# MV500-BASIC-TOP.net
KiCad netlist of a schematic drawn in EAGLE
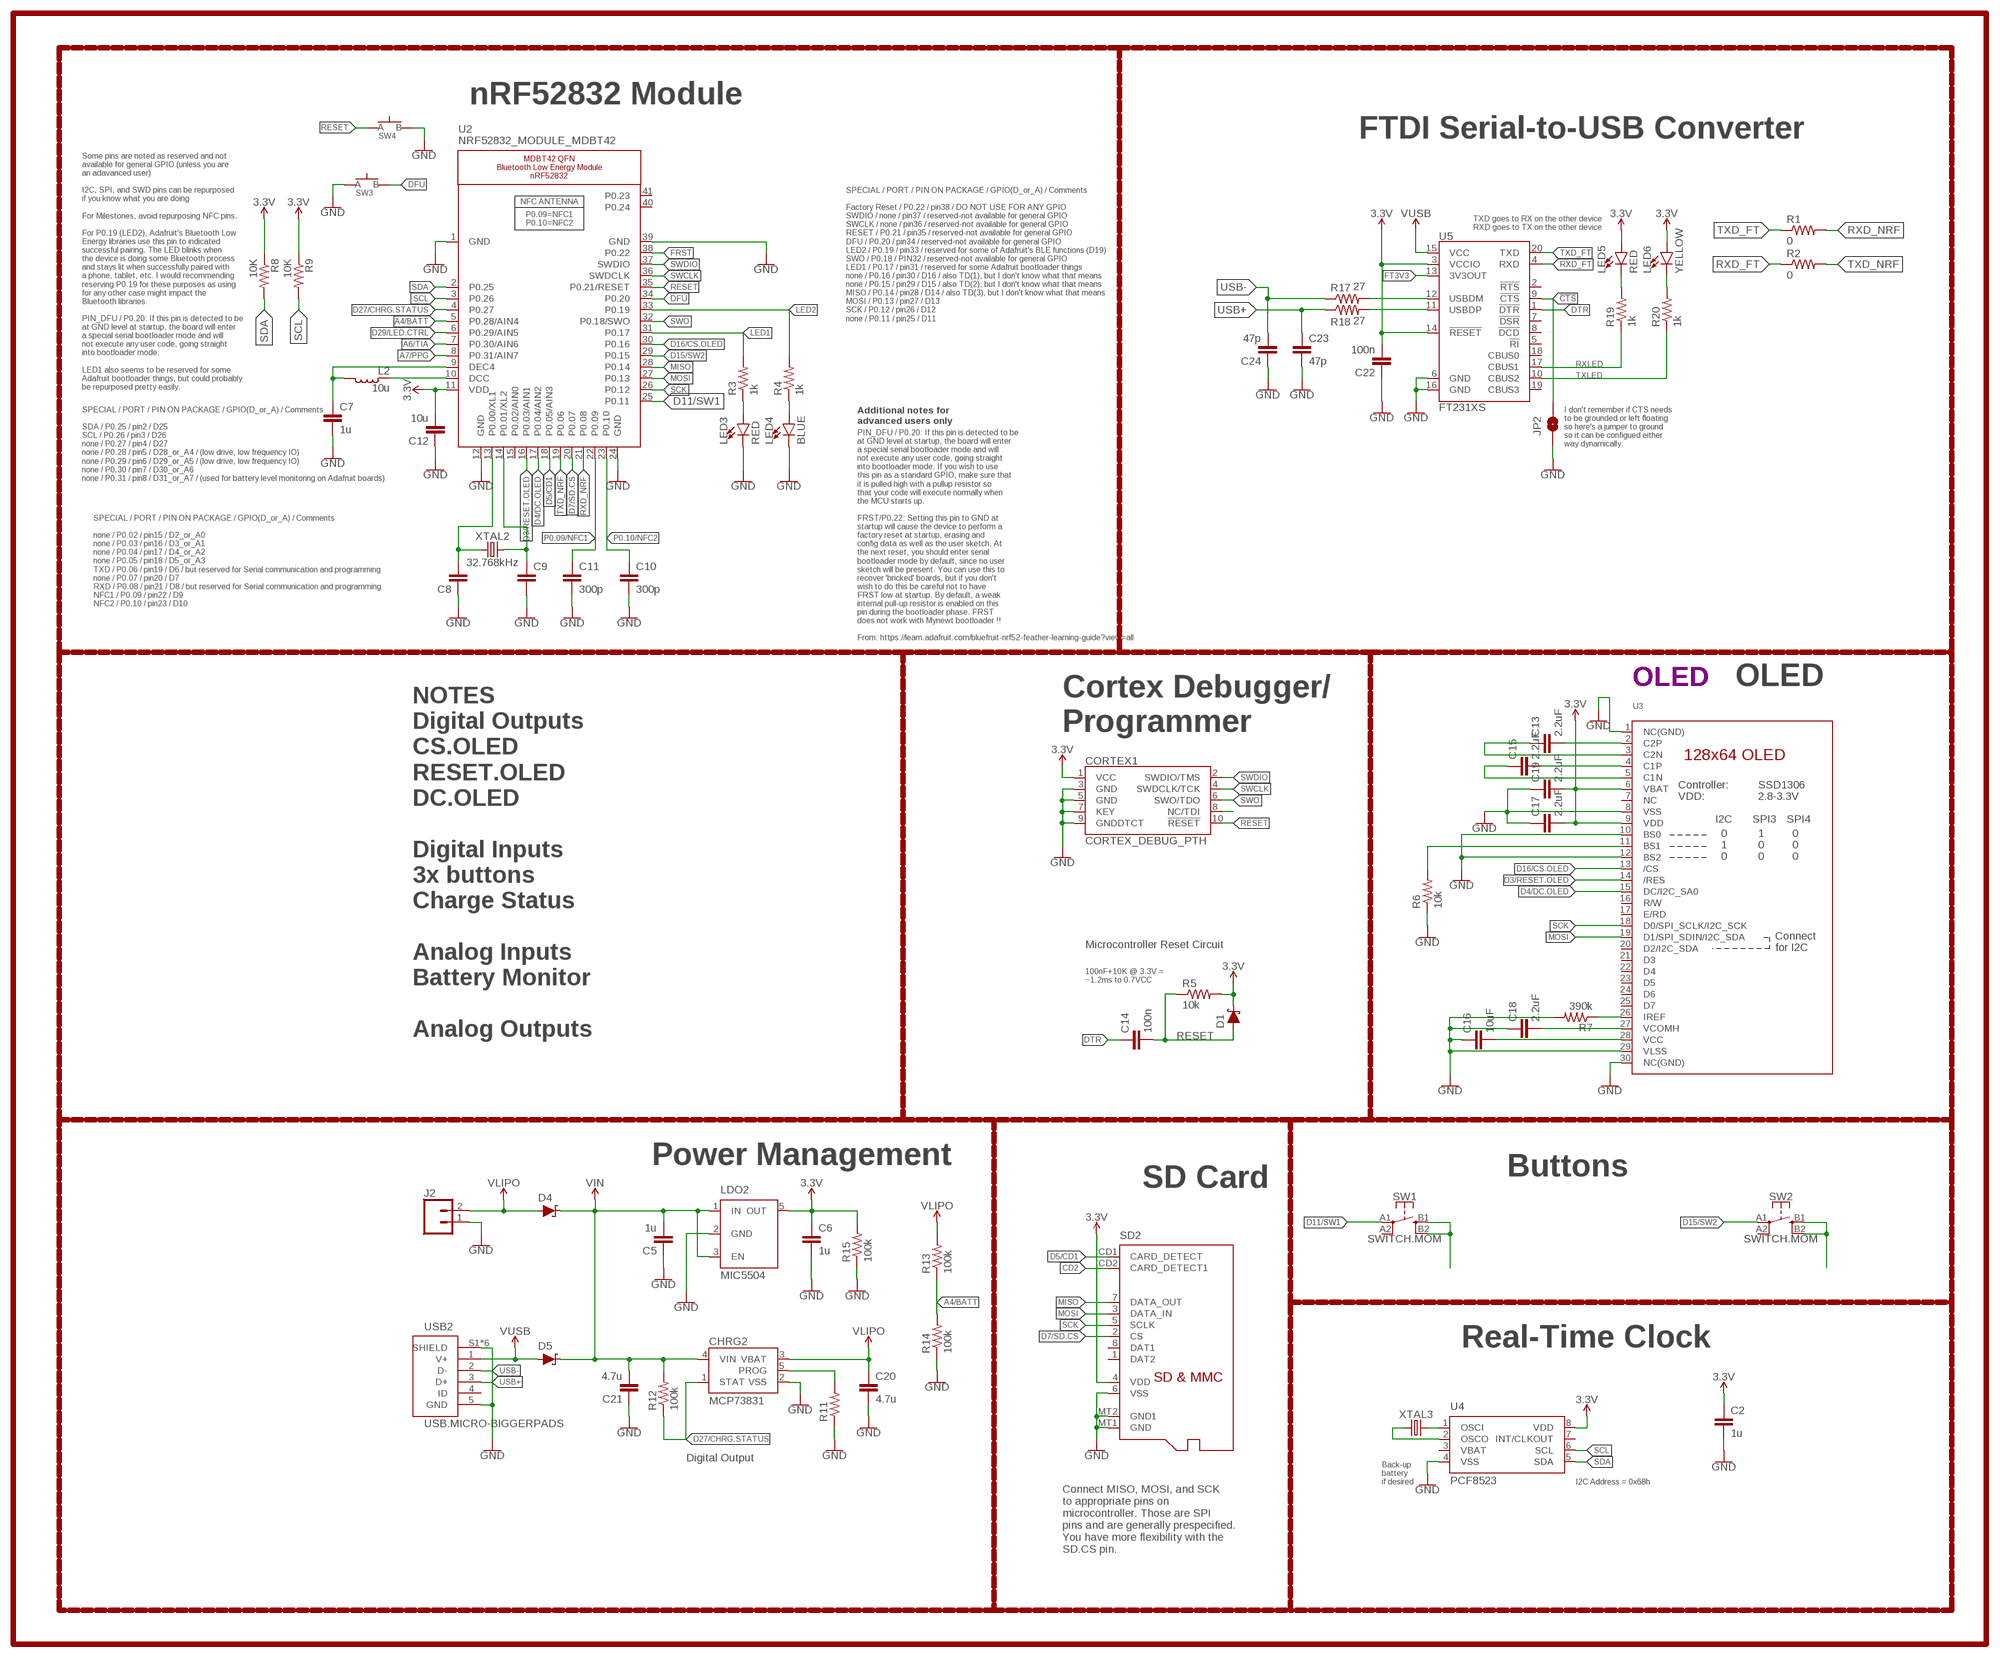
[diagram p0: schematic, sheet 1]

(export (version "E")
  (design (tool "Eeschema 10.0.6"))
  (components
    (comp (ref "C2")
      (value "1u")
      (footprint "eagle-import:C0603")
      (libsource (lib "eagle-import") (part "CAPACITOR0603"))
    )
    (comp (ref "C5")
      (value "1u")
      (footprint "eagle-import:C0603")
      (libsource (lib "eagle-import") (part "CAPACITOR0603"))
    )
    (comp (ref "C6")
      (value "1u")
      (footprint "eagle-import:C0603")
      (libsource (lib "eagle-import") (part "CAPACITOR0603"))
    )
    (comp (ref "C7")
      (value "1u")
      (footprint "eagle-import:C0603")
      (libsource (lib "eagle-import") (part "CAPACITOR0603"))
    )
    (comp (ref "C8")
      (value "CAPACITOR0603")
      (footprint "eagle-import:C0603")
      (libsource (lib "eagle-import") (part "CAPACITOR0603"))
    )
    (comp (ref "C9")
      (value "CAPACITOR0603")
      (footprint "eagle-import:C0603")
      (libsource (lib "eagle-import") (part "CAPACITOR0603"))
    )
    (comp (ref "C10")
      (value "300p")
      (footprint "eagle-import:C0603")
      (libsource (lib "eagle-import") (part "CAPACITOR0603"))
    )
    (comp (ref "C11")
      (value "300p")
      (footprint "eagle-import:C0603")
      (libsource (lib "eagle-import") (part "CAPACITOR0603"))
    )
    (comp (ref "C12")
      (value "10u")
      (footprint "eagle-import:C0805")
      (libsource (lib "eagle-import") (part "CAPACITOR0805"))
    )
    (comp (ref "C13")
      (value "2.2uF")
      (footprint "eagle-import:C0402")
      (libsource (lib "eagle-import") (part "CAPACITOR0402"))
    )
    (comp (ref "C14")
      (value "100n")
      (footprint "eagle-import:C0603")
      (libsource (lib "eagle-import") (part "CAPACITOR0603"))
    )
    (comp (ref "C15")
      (value "2.2uF")
      (footprint "eagle-import:C0402")
      (libsource (lib "eagle-import") (part "CAPACITOR0402"))
    )
    (comp (ref "C16")
      (value "10uF")
      (footprint "eagle-import:C0603")
      (libsource (lib "eagle-import") (part "CAPACITOR0603"))
    )
    (comp (ref "C17")
      (value "2.2uF")
      (footprint "eagle-import:C0402")
      (libsource (lib "eagle-import") (part "CAPACITOR0402"))
    )
    (comp (ref "C18")
      (value "2.2uF")
      (footprint "eagle-import:C0402")
      (libsource (lib "eagle-import") (part "CAPACITOR0402"))
    )
    (comp (ref "C19")
      (value "2.2uF")
      (footprint "eagle-import:C0402")
      (libsource (lib "eagle-import") (part "CAPACITOR0402"))
    )
    (comp (ref "C20")
      (value "4.7u")
      (footprint "eagle-import:C0603")
      (libsource (lib "eagle-import") (part "CAPACITOR0603"))
    )
    (comp (ref "C21")
      (value "4.7u")
      (footprint "eagle-import:C0603")
      (libsource (lib "eagle-import") (part "CAPACITOR0603"))
    )
    (comp (ref "C22")
      (value "100n")
      (footprint "eagle-import:C0603")
      (libsource (lib "eagle-import") (part "CAPACITOR0603"))
    )
    (comp (ref "C23")
      (value "47p")
      (footprint "eagle-import:C0603")
      (libsource (lib "eagle-import") (part "CAPACITOR0603"))
    )
    (comp (ref "C24")
      (value "47p")
      (footprint "eagle-import:C0603")
      (libsource (lib "eagle-import") (part "CAPACITOR0603"))
    )
    (comp (ref "CHRG2")
      (value "MCP73831")
      (footprint "eagle-import:SOT23-5")
      (libsource (lib "eagle-import") (part "MCP73831"))
    )
    (comp (ref "CORTEX1")
      (value "CORTEX_DEBUG_PTH")
      (footprint "eagle-import:2X5-PTH-1.27MM")
      (libsource (lib "eagle-import") (part "CORTEX_DEBUG_PTH"))
    )
    (comp (ref "D1")
      (value "SCHOTTKY-USC")
      (footprint "eagle-import:USC")
      (libsource (lib "eagle-import") (part "SCHOTTKY-USC"))
    )
    (comp (ref "D4")
      (value "SCHOTTKY-USC")
      (footprint "eagle-import:USC")
      (libsource (lib "eagle-import") (part "SCHOTTKY-USC"))
    )
    (comp (ref "D5")
      (value "SCHOTTKY-USC")
      (footprint "eagle-import:USC")
      (libsource (lib "eagle-import") (part "SCHOTTKY-USC"))
    )
    (comp (ref "J2")
      (value "CONN_02")
      (footprint "eagle-import:1X02")
      (libsource (lib "eagle-import") (part "CONN_02"))
    )
    (comp (ref "JP2")
      (value "JUMPER-SMT_2_NO_SILK")
      (footprint "eagle-import:SMT-JUMPER_2_NO_SILK")
      (libsource (lib "eagle-import") (part "JUMPER-SMT_2_NO_SILK"))
    )
    (comp (ref "L2")
      (value "10u")
      (footprint "eagle-import:L0603")
      (libsource (lib "eagle-import") (part "INDUCTOR0603"))
    )
    (comp (ref "LDO2")
      (value "MIC5504")
      (footprint "eagle-import:SOT23-5")
      (libsource (lib "eagle-import") (part "MIC5504"))
    )
    (comp (ref "LED3")
      (value "RED")
      (footprint "eagle-import:LED-0603")
      (libsource (lib "eagle-import") (part "LED0603"))
    )
    (comp (ref "LED4")
      (value "BLUE")
      (footprint "eagle-import:LED-0603")
      (libsource (lib "eagle-import") (part "LED0603"))
    )
    (comp (ref "LED5")
      (value "RED")
      (footprint "eagle-import:LED-0603")
      (libsource (lib "eagle-import") (part "LED0603"))
    )
    (comp (ref "LED6")
      (value "YELLOW")
      (footprint "eagle-import:LED-0603")
      (libsource (lib "eagle-import") (part "LED0603"))
    )
    (comp (ref "R1")
      (value "0")
      (footprint "eagle-import:R0603")
      (libsource (lib "eagle-import") (part "RESISTOR0603"))
    )
    (comp (ref "R2")
      (value "0")
      (footprint "eagle-import:R0603")
      (libsource (lib "eagle-import") (part "RESISTOR0603"))
    )
    (comp (ref "R3")
      (value "1k")
      (footprint "eagle-import:R0603")
      (libsource (lib "eagle-import") (part "RESISTOR0603"))
    )
    (comp (ref "R4")
      (value "1k")
      (footprint "eagle-import:R0603")
      (libsource (lib "eagle-import") (part "RESISTOR0603"))
    )
    (comp (ref "R5")
      (value "10k")
      (footprint "eagle-import:R0603")
      (libsource (lib "eagle-import") (part "RESISTOR0603"))
    )
    (comp (ref "R6")
      (value "10k")
      (footprint "eagle-import:R0603")
      (libsource (lib "eagle-import") (part "RESISTOR0603"))
    )
    (comp (ref "R7")
      (value "390k")
      (footprint "eagle-import:R0603")
      (libsource (lib "eagle-import") (part "RESISTOR0603"))
    )
    (comp (ref "R8")
      (value "10K")
      (footprint "eagle-import:R0603")
      (libsource (lib "eagle-import") (part "RESISTOR0603"))
    )
    (comp (ref "R9")
      (value "10K")
      (footprint "eagle-import:R0603")
      (libsource (lib "eagle-import") (part "RESISTOR0603"))
    )
    (comp (ref "R11")
      (value "RESISTOR0603")
      (footprint "eagle-import:R0603")
      (libsource (lib "eagle-import") (part "RESISTOR0603"))
    )
    (comp (ref "R12")
      (value "100k")
      (footprint "eagle-import:R0603")
      (libsource (lib "eagle-import") (part "RESISTOR0603"))
    )
    (comp (ref "R13")
      (value "100k")
      (footprint "eagle-import:R0603")
      (libsource (lib "eagle-import") (part "RESISTOR0603"))
    )
    (comp (ref "R14")
      (value "100k")
      (footprint "eagle-import:R0603")
      (libsource (lib "eagle-import") (part "RESISTOR0603"))
    )
    (comp (ref "R15")
      (value "100k")
      (footprint "eagle-import:R0603")
      (libsource (lib "eagle-import") (part "RESISTOR0603"))
    )
    (comp (ref "R17")
      (value "27")
      (footprint "eagle-import:R0603")
      (libsource (lib "eagle-import") (part "RESISTOR0603"))
    )
    (comp (ref "R18")
      (value "27")
      (footprint "eagle-import:R0603")
      (libsource (lib "eagle-import") (part "RESISTOR0603"))
    )
    (comp (ref "R19")
      (value "1k")
      (footprint "eagle-import:R0603")
      (libsource (lib "eagle-import") (part "RESISTOR0603"))
    )
    (comp (ref "R20")
      (value "1k")
      (footprint "eagle-import:R0603")
      (libsource (lib "eagle-import") (part "RESISTOR0603"))
    )
    (comp (ref "SD2")
      (value "MICROSD")
      (footprint "eagle-import:MICROSD")
      (libsource (lib "eagle-import") (part "MICROSD"))
    )
    (comp (ref "SW1")
      (value "SWITCH.MOM")
      (footprint "eagle-import:TACTILE_SWITCH_SMD_6.2MM_TALL")
      (libsource (lib "eagle-import") (part "SWITCH.MOM"))
    )
    (comp (ref "SW2")
      (value "SWITCH.MOM")
      (footprint "eagle-import:TACTILE_SWITCH_SMD_6.2MM_TALL")
      (libsource (lib "eagle-import") (part "SWITCH.MOM"))
    )
    (comp (ref "SW3")
      (value "SPST-PTS830GG140-COPY.1-3")
      (footprint "eagle-import:BUTTON-GULLWING")
      (libsource (lib "eagle-import") (part "SPST-PTS830GG140-COPY.1-3"))
    )
    (comp (ref "SW4")
      (value "SPST-PTS830GG140-COPY.1-3")
      (footprint "eagle-import:BUTTON-GULLWING")
      (libsource (lib "eagle-import") (part "SPST-PTS830GG140-COPY.1-3"))
    )
    (comp (ref "U2")
      (value "NRF52832_MODULE_MDBT42")
      (footprint "eagle-import:BLE_MODULE_RAYTAC_MDBT42")
      (libsource (lib "eagle-import") (part "NRF52832_MODULE_MDBT42"))
    )
    (comp (ref "U3")
      (value "DISP_OLED_UG-2864HSWEG01-NO-WRAPAROUND")
      (footprint "eagle-import:UG-2864HSWEG01_0.96IN_NO-WRAPAROUND")
      (libsource (lib "eagle-import") (part "DISP_OLED_UG-2864HSWEG01-NO-WRAPAROUND"))
    )
    (comp (ref "U4")
      (value "PCF8523")
      (footprint "eagle-import:SO8")
      (libsource (lib "eagle-import") (part "PCF8523"))
    )
    (comp (ref "U5")
      (value "FT231XS")
      (footprint "eagle-import:SSOP20_L")
      (libsource (lib "eagle-import") (part "FT231XS"))
    )
    (comp (ref "USB2")
      (value "USB.MICRO-BIGGERPADS")
      (footprint "eagle-import:USB-MICRO-01.BIGGERPADS")
      (libsource (lib "eagle-import") (part "USB.MICRO-BIGGERPADS"))
    )
    (comp (ref "XTAL2")
      (value "32.768kHz")
      (footprint "eagle-import:2-SMD.NOLEAD.2.0MMTO1.2MM")
      (libsource (lib "eagle-import") (part "CRYSTALECS-.327-12.5-12-C-TR"))
    )
    (comp (ref "XTAL3")
      (value "32.7680kHz")
      (footprint "eagle-import:2-SMD.NOLEAD.2.0MMTO1.2MM")
      (fields (field (name "FREQ") "32.7680KHZ"))
      (libsource (lib "eagle-import") (part "CRYSTALECS-.327-12.5-12-C-TR"))
    )
  )
  (nets
    (net (code "1") (name "/RXLED") (class "Default")
      (node (ref "R19") (pin "1") (pinfunction "1_1") (pintype "passive"))
      (node (ref "U5") (pin "17") (pinfunction "CBUS1_17") (pintype "bidirectional"))
    )
    (net (code "2") (name "/TXLED") (class "Default")
      (node (ref "R20") (pin "1") (pinfunction "1_1") (pintype "passive"))
      (node (ref "U5") (pin "10") (pinfunction "CBUS2_10") (pintype "bidirectional"))
    )
    (net (code "3") (name "/VBAT") (class "Default")
      (node (ref "U4") (pin "3") (pinfunction "VBAT_3") (pintype "power_in"))
    )
    (net (code "4") (name "/~{CTS}") (class "Default")
      (node (ref "JP2") (pin "2") (pinfunction "2_2") (pintype "passive"))
      (node (ref "U5") (pin "9") (pinfunction "~{CTS}_9") (pintype "bidirectional"))
    )
    (net (code "5") (name "3.3V") (class "Default")
      (node (ref "C12") (pin "2") (pinfunction "2_2") (pintype "passive"))
      (node (ref "C17") (pin "2") (pinfunction "2_2") (pintype "passive"))
      (node (ref "C19") (pin "2") (pinfunction "2_2") (pintype "passive"))
      (node (ref "C2") (pin "1") (pinfunction "1_1") (pintype "passive"))
      (node (ref "C22") (pin "2") (pinfunction "2_2") (pintype "passive"))
      (node (ref "C6") (pin "1") (pinfunction "1_1") (pintype "passive"))
      (node (ref "CORTEX1") (pin "1") (pinfunction "VCC_1") (pintype "bidirectional"))
      (node (ref "D1") (pin "-") (pinfunction "C_-") (pintype "passive"))
      (node (ref "LDO2") (pin "5") (pinfunction "OUT_5") (pintype "bidirectional"))
      (node (ref "LED5") (pin "A") (pinfunction "A_A") (pintype "passive"))
      (node (ref "LED6") (pin "A") (pinfunction "A_A") (pintype "passive"))
      (node (ref "R15") (pin "2") (pinfunction "2_2") (pintype "passive"))
      (node (ref "R5") (pin "2") (pinfunction "2_2") (pintype "passive"))
      (node (ref "R8") (pin "1") (pinfunction "1_1") (pintype "passive"))
      (node (ref "R9") (pin "1") (pinfunction "1_1") (pintype "passive"))
      (node (ref "SD2") (pin "4") (pinfunction "VDD_4") (pintype "power_in"))
      (node (ref "U2") (pin "11") (pinfunction "VDD_11") (pintype "bidirectional"))
      (node (ref "U3") (pin "6") (pinfunction "VBAT_6") (pintype "input"))
      (node (ref "U3") (pin "9") (pinfunction "VDD_9") (pintype "power_in"))
      (node (ref "U4") (pin "8") (pinfunction "VDD_8") (pintype "power_in"))
      (node (ref "U5") (pin "14") (pinfunction "~{RESET}_14") (pintype "bidirectional"))
      (node (ref "U5") (pin "3") (pinfunction "VCCIO_3") (pintype "bidirectional"))
    )
    (net (code "6") (name "A4{slash}BATT") (class "Default")
      (node (ref "R13") (pin "1") (pinfunction "1_1") (pintype "passive"))
      (node (ref "R14") (pin "2") (pinfunction "2_2") (pintype "passive"))
      (node (ref "U2") (pin "5") (pinfunction "P0.28/AIN4_5") (pintype "bidirectional"))
    )
    (net (code "7") (name "A6{slash}TIA") (class "Default")
      (node (ref "U2") (pin "7") (pinfunction "P0.30/AIN6_7") (pintype "bidirectional"))
    )
    (net (code "8") (name "A7{slash}PPG") (class "Default")
      (node (ref "U2") (pin "8") (pinfunction "P0.31/AIN7_8") (pintype "bidirectional"))
    )
    (net (code "9") (name "CD2") (class "Default")
      (node (ref "SD2") (pin "CD2") (pinfunction "CARD_DETECT1_CD2") (pintype "passive"))
    )
    (net (code "10") (name "D3{slash}RESET.OLED") (class "Default")
      (node (ref "U2") (pin "16") (pinfunction "P0.03/AIN1_16") (pintype "bidirectional"))
      (node (ref "U3") (pin "14") (pinfunction "/RES_14") (pintype "input"))
    )
    (net (code "11") (name "D4{slash}DC.OLED") (class "Default")
      (node (ref "U2") (pin "17") (pinfunction "P0.04/AIN2_17") (pintype "bidirectional"))
      (node (ref "U3") (pin "15") (pinfunction "DC/I2C_SA0_15") (pintype "input"))
    )
    (net (code "12") (name "D5{slash}CD1") (class "Default")
      (node (ref "SD2") (pin "CD1") (pinfunction "CARD_DETECT_CD1") (pintype "passive"))
      (node (ref "U2") (pin "18") (pinfunction "P0.05/AIN3_18") (pintype "bidirectional"))
    )
    (net (code "13") (name "D7{slash}SD.CS") (class "Default")
      (node (ref "SD2") (pin "2") (pinfunction "CS_2") (pintype "input"))
      (node (ref "U2") (pin "20") (pinfunction "P0.07_20") (pintype "bidirectional"))
    )
    (net (code "14") (name "D11{slash}SW1") (class "Default")
      (node (ref "SW1") (pin "A1") (pinfunction "1_A1") (pintype "passive"))
      (node (ref "U2") (pin "25") (pinfunction "P0.11_25") (pintype "bidirectional"))
    )
    (net (code "15") (name "D15{slash}SW2") (class "Default")
      (node (ref "SW2") (pin "A1") (pinfunction "1_A1") (pintype "passive"))
      (node (ref "U2") (pin "29") (pinfunction "P0.15_29") (pintype "bidirectional"))
    )
    (net (code "16") (name "D16{slash}CS.OLED") (class "Default")
      (node (ref "U2") (pin "30") (pinfunction "P0.16_30") (pintype "bidirectional"))
      (node (ref "U3") (pin "13") (pinfunction "/CS_13") (pintype "input"))
    )
    (net (code "17") (name "D27{slash}CHRG.STATUS") (class "Default")
      (node (ref "CHRG2") (pin "1") (pinfunction "STAT_1") (pintype "output"))
      (node (ref "R12") (pin "1") (pinfunction "1_1") (pintype "passive"))
      (node (ref "U2") (pin "4") (pinfunction "P0.27_4") (pintype "bidirectional"))
    )
    (net (code "18") (name "D29{slash}LED.CTRL") (class "Default")
      (node (ref "U2") (pin "6") (pinfunction "P0.29/AIN5_6") (pintype "bidirectional"))
    )
    (net (code "19") (name "DFU") (class "Default")
      (node (ref "SW3") (pin "3") (pinfunction "B_3") (pintype "bidirectional"))
      (node (ref "U2") (pin "34") (pinfunction "P0.20_34") (pintype "bidirectional"))
    )
    (net (code "20") (name "DTR") (class "Default")
      (node (ref "C14") (pin "1") (pinfunction "1_1") (pintype "passive"))
      (node (ref "U5") (pin "1") (pinfunction "~{DTR}_1") (pintype "bidirectional"))
    )
    (net (code "21") (name "FRST") (class "Default")
      (node (ref "U2") (pin "38") (pinfunction "P0.22_38") (pintype "bidirectional"))
    )
    (net (code "22") (name "FT3V3") (class "Default")
      (node (ref "U5") (pin "13") (pinfunction "3V3OUT_13") (pintype "bidirectional"))
    )
    (net (code "23") (name "GND") (class "Default")
      (node (ref "C10") (pin "2") (pinfunction "2_2") (pintype "passive"))
      (node (ref "C11") (pin "2") (pinfunction "2_2") (pintype "passive"))
      (node (ref "C12") (pin "1") (pinfunction "1_1") (pintype "passive"))
      (node (ref "C16") (pin "1") (pinfunction "1_1") (pintype "passive"))
      (node (ref "C17") (pin "1") (pinfunction "1_1") (pintype "passive"))
      (node (ref "C18") (pin "1") (pinfunction "1_1") (pintype "passive"))
      (node (ref "C19") (pin "1") (pinfunction "1_1") (pintype "passive"))
      (node (ref "C2") (pin "2") (pinfunction "2_2") (pintype "passive"))
      (node (ref "C20") (pin "2") (pinfunction "2_2") (pintype "passive"))
      (node (ref "C21") (pin "1") (pinfunction "1_1") (pintype "passive"))
      (node (ref "C22") (pin "1") (pinfunction "1_1") (pintype "passive"))
      (node (ref "C23") (pin "2") (pinfunction "2_2") (pintype "passive"))
      (node (ref "C24") (pin "1") (pinfunction "1_1") (pintype "passive"))
      (node (ref "C5") (pin "1") (pinfunction "1_1") (pintype "passive"))
      (node (ref "C6") (pin "2") (pinfunction "2_2") (pintype "passive"))
      (node (ref "C7") (pin "2") (pinfunction "2_2") (pintype "passive"))
      (node (ref "C8") (pin "1") (pinfunction "1_1") (pintype "passive"))
      (node (ref "C9") (pin "2") (pinfunction "2_2") (pintype "passive"))
      (node (ref "CHRG2") (pin "2") (pinfunction "VSS_2") (pintype "power_in"))
      (node (ref "CORTEX1") (pin "3") (pinfunction "GND_3") (pintype "bidirectional"))
      (node (ref "CORTEX1") (pin "5") (pinfunction "GND_5") (pintype "bidirectional"))
      (node (ref "CORTEX1") (pin "7") (pinfunction "KEY_7") (pintype "bidirectional"))
      (node (ref "CORTEX1") (pin "9") (pinfunction "GNDDTCT_9") (pintype "bidirectional"))
      (node (ref "J2") (pin "1") (pinfunction "1_1") (pintype "passive"))
      (node (ref "JP2") (pin "1") (pinfunction "1_1") (pintype "passive"))
      (node (ref "LDO2") (pin "2") (pinfunction "GND_2") (pintype "bidirectional"))
      (node (ref "LED3") (pin "C") (pinfunction "C_C") (pintype "passive"))
      (node (ref "LED4") (pin "C") (pinfunction "C_C") (pintype "passive"))
      (node (ref "R11") (pin "1") (pinfunction "1_1") (pintype "passive"))
      (node (ref "R14") (pin "1") (pinfunction "1_1") (pintype "passive"))
      (node (ref "R15") (pin "1") (pinfunction "1_1") (pintype "passive"))
      (node (ref "R6") (pin "1") (pinfunction "1_1") (pintype "passive"))
      (node (ref "R7") (pin "2") (pinfunction "2_2") (pintype "passive"))
      (node (ref "SD2") (pin "6") (pinfunction "VSS_6") (pintype "power_in"))
      (node (ref "SD2") (pin "MT1") (pinfunction "GND_MT1") (pintype "power_in"))
      (node (ref "SD2") (pin "MT2") (pinfunction "GND1_MT2") (pintype "power_in"))
      (node (ref "SW3") (pin "1") (pinfunction "A_1") (pintype "bidirectional"))
      (node (ref "SW4") (pin "3") (pinfunction "B_3") (pintype "bidirectional"))
      (node (ref "U2") (pin "1") (pinfunction "GND_1") (pintype "bidirectional"))
      (node (ref "U2") (pin "12") (pinfunction "GND_12") (pintype "bidirectional"))
      (node (ref "U2") (pin "24") (pinfunction "GND_24") (pintype "bidirectional"))
      (node (ref "U2") (pin "39") (pinfunction "GND_39") (pintype "bidirectional"))
      (node (ref "U3") (pin "1") (pinfunction "NC(GND)_1") (pintype "input"))
      (node (ref "U3") (pin "10") (pinfunction "BS0_10") (pintype "input"))
      (node (ref "U3") (pin "12") (pinfunction "BS2_12") (pintype "input"))
      (node (ref "U3") (pin "29") (pinfunction "VLSS_29") (pintype "power_in"))
      (node (ref "U3") (pin "30") (pinfunction "NC(GND)_30") (pintype "input"))
      (node (ref "U3") (pin "8") (pinfunction "VSS_8") (pintype "power_in"))
      (node (ref "U4") (pin "4") (pinfunction "VSS_4") (pintype "power_in"))
      (node (ref "U5") (pin "16") (pinfunction "GND_16") (pintype "bidirectional"))
      (node (ref "U5") (pin "6") (pinfunction "GND_6") (pintype "bidirectional"))
      (node (ref "USB2") (pin "5") (pinfunction "GND_5") (pintype "bidirectional"))
      (node (ref "USB2") (pin "S1") (pinfunction "SHIELD_S1") (pintype "bidirectional"))
      (node (ref "USB2") (pin "S2") (pinfunction "SHIELD_S2") (pintype "bidirectional"))
      (node (ref "USB2") (pin "S3") (pinfunction "SHIELD_S3") (pintype "bidirectional"))
      (node (ref "USB2") (pin "S4") (pinfunction "SHIELD_S4") (pintype "bidirectional"))
      (node (ref "USB2") (pin "S5") (pinfunction "SHIELD_S5") (pintype "bidirectional"))
      (node (ref "USB2") (pin "S6") (pinfunction "SHIELD_S6") (pintype "bidirectional"))
    )
    (net (code "24") (name "LED1") (class "Default")
      (node (ref "R3") (pin "2") (pinfunction "2_2") (pintype "passive"))
      (node (ref "U2") (pin "31") (pinfunction "P0.17_31") (pintype "bidirectional"))
    )
    (net (code "25") (name "LED2") (class "Default")
      (node (ref "R4") (pin "2") (pinfunction "2_2") (pintype "passive"))
      (node (ref "U2") (pin "33") (pinfunction "P0.19_33") (pintype "bidirectional"))
    )
    (net (code "26") (name "MISO") (class "Default")
      (node (ref "SD2") (pin "7") (pinfunction "DATA_OUT_7") (pintype "output"))
      (node (ref "U2") (pin "28") (pinfunction "P0.14_28") (pintype "bidirectional"))
    )
    (net (code "27") (name "MOSI") (class "Default")
      (node (ref "SD2") (pin "3") (pinfunction "DATA_IN_3") (pintype "input"))
      (node (ref "U2") (pin "27") (pinfunction "P0.13_27") (pintype "bidirectional"))
      (node (ref "U3") (pin "19") (pinfunction "D1/SPI_SDIN/I2C_SDA_19") (pintype "bidirectional"))
    )
    (net (code "28") (name "Net-(CHRG2-PROG)") (class "Default")
      (node (ref "CHRG2") (pin "5") (pinfunction "PROG_5") (pintype "input"))
      (node (ref "R11") (pin "2") (pinfunction "2_2") (pintype "passive"))
    )
    (net (code "29") (name "Net-(LED3-PadA)") (class "Default")
      (node (ref "LED3") (pin "A") (pinfunction "A_A") (pintype "passive"))
      (node (ref "R3") (pin "1") (pinfunction "1_1") (pintype "passive"))
    )
    (net (code "30") (name "Net-(LED4-PadA)") (class "Default")
      (node (ref "LED4") (pin "A") (pinfunction "A_A") (pintype "passive"))
      (node (ref "R4") (pin "1") (pinfunction "1_1") (pintype "passive"))
    )
    (net (code "31") (name "Net-(LED5-PadC)") (class "Default")
      (node (ref "LED5") (pin "C") (pinfunction "C_C") (pintype "passive"))
      (node (ref "R19") (pin "2") (pinfunction "2_2") (pintype "passive"))
    )
    (net (code "32") (name "Net-(LED6-PadC)") (class "Default")
      (node (ref "LED6") (pin "C") (pinfunction "C_C") (pintype "passive"))
      (node (ref "R20") (pin "2") (pinfunction "2_2") (pintype "passive"))
    )
    (net (code "33") (name "Net-(SW1-3)") (class "Default")
      (node (ref "SW1") (pin "B1") (pinfunction "3_B1") (pintype "passive"))
      (node (ref "SW1") (pin "B2") (pinfunction "4_B2") (pintype "passive"))
    )
    (net (code "34") (name "Net-(SW2-3)") (class "Default")
      (node (ref "SW2") (pin "B1") (pinfunction "3_B1") (pintype "passive"))
      (node (ref "SW2") (pin "B2") (pinfunction "4_B2") (pintype "passive"))
    )
    (net (code "35") (name "Net-(U2-DCC)") (class "Default")
      (node (ref "L2") (pin "1") (pinfunction "1_1") (pintype "passive"))
      (node (ref "U2") (pin "10") (pinfunction "DCC_10") (pintype "bidirectional"))
    )
    (net (code "36") (name "Net-(U2-DEC4)") (class "Default")
      (node (ref "C7") (pin "1") (pinfunction "1_1") (pintype "passive"))
      (node (ref "L2") (pin "2") (pinfunction "2_2") (pintype "passive"))
      (node (ref "U2") (pin "9") (pinfunction "DEC4_9") (pintype "bidirectional"))
    )
    (net (code "37") (name "Net-(U2-P0.00{slash}XL1)") (class "Default")
      (node (ref "C8") (pin "2") (pinfunction "2_2") (pintype "passive"))
      (node (ref "U2") (pin "13") (pinfunction "P0.00/XL1_13") (pintype "bidirectional"))
      (node (ref "XTAL2") (pin "P$1") (pinfunction "1_P$1") (pintype "passive"))
    )
    (net (code "38") (name "Net-(U2-P0.01{slash}XL2)") (class "Default")
      (node (ref "C9") (pin "1") (pinfunction "1_1") (pintype "passive"))
      (node (ref "U2") (pin "14") (pinfunction "P0.01/XL2_14") (pintype "bidirectional"))
      (node (ref "XTAL2") (pin "P$2") (pinfunction "2_P$2") (pintype "passive"))
    )
    (net (code "39") (name "Net-(U3-BS1)") (class "Default")
      (node (ref "R6") (pin "2") (pinfunction "2_2") (pintype "passive"))
      (node (ref "U3") (pin "11") (pinfunction "BS1_11") (pintype "input"))
    )
    (net (code "40") (name "Net-(U3-C1N)") (class "Default")
      (node (ref "C15") (pin "1") (pinfunction "1_1") (pintype "passive"))
      (node (ref "U3") (pin "5") (pinfunction "C1N_5") (pintype "input"))
    )
    (net (code "41") (name "Net-(U3-C1P)") (class "Default")
      (node (ref "C15") (pin "2") (pinfunction "2_2") (pintype "passive"))
      (node (ref "U3") (pin "4") (pinfunction "C1P_4") (pintype "input"))
    )
    (net (code "42") (name "Net-(U3-C2N)") (class "Default")
      (node (ref "C13") (pin "1") (pinfunction "1_1") (pintype "passive"))
      (node (ref "U3") (pin "3") (pinfunction "C2N_3") (pintype "input"))
    )
    (net (code "43") (name "Net-(U3-C2P)") (class "Default")
      (node (ref "C13") (pin "2") (pinfunction "2_2") (pintype "passive"))
      (node (ref "U3") (pin "2") (pinfunction "C2P_2") (pintype "input"))
    )
    (net (code "44") (name "Net-(U3-IREF)") (class "Default")
      (node (ref "R7") (pin "1") (pinfunction "1_1") (pintype "passive"))
      (node (ref "U3") (pin "26") (pinfunction "IREF_26") (pintype "input"))
    )
    (net (code "45") (name "Net-(U3-VCC)") (class "Default")
      (node (ref "C16") (pin "2") (pinfunction "2_2") (pintype "passive"))
      (node (ref "U3") (pin "28") (pinfunction "VCC_28") (pintype "power_in"))
    )
    (net (code "46") (name "Net-(U3-VCOMH)") (class "Default")
      (node (ref "C18") (pin "2") (pinfunction "2_2") (pintype "passive"))
      (node (ref "U3") (pin "27") (pinfunction "VCOMH_27") (pintype "output"))
    )
    (net (code "47") (name "Net-(U4-OSCI)") (class "Default")
      (node (ref "U4") (pin "1") (pinfunction "OSCI_1") (pintype "bidirectional"))
      (node (ref "XTAL3") (pin "P$2") (pinfunction "2_P$2") (pintype "passive"))
    )
    (net (code "48") (name "Net-(U4-OSCO)") (class "Default")
      (node (ref "U4") (pin "2") (pinfunction "OSCO_2") (pintype "bidirectional"))
      (node (ref "XTAL3") (pin "P$1") (pinfunction "1_P$1") (pintype "passive"))
    )
    (net (code "49") (name "Net-(U5-USBDM)") (class "Default")
      (node (ref "R17") (pin "2") (pinfunction "2_2") (pintype "passive"))
      (node (ref "U5") (pin "12") (pinfunction "USBDM_12") (pintype "bidirectional"))
    )
    (net (code "50") (name "Net-(U5-USBDP)") (class "Default")
      (node (ref "R18") (pin "2") (pinfunction "2_2") (pintype "passive"))
      (node (ref "U5") (pin "11") (pinfunction "USBDP_11") (pintype "bidirectional"))
    )
    (net (code "51") (name "P0.09{slash}NFC1") (class "Default")
      (node (ref "C11") (pin "1") (pinfunction "1_1") (pintype "passive"))
      (node (ref "U2") (pin "22") (pinfunction "P0.09_22") (pintype "bidirectional"))
    )
    (net (code "52") (name "P0.10{slash}NFC2") (class "Default")
      (node (ref "C10") (pin "1") (pinfunction "1_1") (pintype "passive"))
      (node (ref "U2") (pin "23") (pinfunction "P0.10_23") (pintype "bidirectional"))
    )
    (net (code "53") (name "RESET") (class "Default")
      (node (ref "C14") (pin "2") (pinfunction "2_2") (pintype "passive"))
      (node (ref "CORTEX1") (pin "10") (pinfunction "~{RESET}_10") (pintype "bidirectional"))
      (node (ref "D1") (pin "+") (pinfunction "A_+") (pintype "passive"))
      (node (ref "R5") (pin "1") (pinfunction "1_1") (pintype "passive"))
      (node (ref "SW4") (pin "1") (pinfunction "A_1") (pintype "bidirectional"))
      (node (ref "U2") (pin "35") (pinfunction "P0.21/RESET_35") (pintype "bidirectional"))
    )
    (net (code "54") (name "RXD_FT") (class "Default")
      (node (ref "R2") (pin "1") (pinfunction "1_1") (pintype "passive"))
      (node (ref "U5") (pin "4") (pinfunction "RXD_4") (pintype "bidirectional"))
    )
    (net (code "55") (name "RXD_NRF") (class "Default")
      (node (ref "R1") (pin "2") (pinfunction "2_2") (pintype "passive"))
      (node (ref "U2") (pin "21") (pinfunction "P0.08_21") (pintype "bidirectional"))
    )
    (net (code "56") (name "SCK") (class "Default")
      (node (ref "SD2") (pin "5") (pinfunction "SCLK_5") (pintype "input"))
      (node (ref "U2") (pin "26") (pinfunction "P0.12_26") (pintype "bidirectional"))
      (node (ref "U3") (pin "18") (pinfunction "D0/SPI_SCLK/I2C_SCK_18") (pintype "bidirectional"))
    )
    (net (code "57") (name "SCL") (class "Default")
      (node (ref "R9") (pin "2") (pinfunction "2_2") (pintype "passive"))
      (node (ref "U2") (pin "3") (pinfunction "P0.26_3") (pintype "bidirectional"))
      (node (ref "U4") (pin "6") (pinfunction "SCL_6") (pintype "bidirectional"))
    )
    (net (code "58") (name "SDA") (class "Default")
      (node (ref "R8") (pin "2") (pinfunction "2_2") (pintype "passive"))
      (node (ref "U2") (pin "2") (pinfunction "P0.25_2") (pintype "bidirectional"))
      (node (ref "U4") (pin "5") (pinfunction "SDA_5") (pintype "bidirectional"))
    )
    (net (code "59") (name "SWCLK") (class "Default")
      (node (ref "CORTEX1") (pin "4") (pinfunction "SWDCLK/TCK_4") (pintype "bidirectional"))
      (node (ref "U2") (pin "36") (pinfunction "SWDCLK_36") (pintype "bidirectional"))
    )
    (net (code "60") (name "SWDIO") (class "Default")
      (node (ref "CORTEX1") (pin "2") (pinfunction "SWDIO/TMS_2") (pintype "bidirectional"))
      (node (ref "U2") (pin "37") (pinfunction "SWDIO_37") (pintype "bidirectional"))
    )
    (net (code "61") (name "SWO") (class "Default")
      (node (ref "CORTEX1") (pin "6") (pinfunction "SWO/TDO_6") (pintype "bidirectional"))
      (node (ref "U2") (pin "32") (pinfunction "P0.18/SWO_32") (pintype "bidirectional"))
    )
    (net (code "62") (name "TXD_FT") (class "Default")
      (node (ref "R1") (pin "1") (pinfunction "1_1") (pintype "passive"))
      (node (ref "U5") (pin "20") (pinfunction "TXD_20") (pintype "bidirectional"))
    )
    (net (code "63") (name "TXD_NRF") (class "Default")
      (node (ref "R2") (pin "2") (pinfunction "2_2") (pintype "passive"))
      (node (ref "U2") (pin "19") (pinfunction "P0.06_19") (pintype "bidirectional"))
    )
    (net (code "64") (name "USB+") (class "Default")
      (node (ref "C23") (pin "1") (pinfunction "1_1") (pintype "passive"))
      (node (ref "R18") (pin "1") (pinfunction "1_1") (pintype "passive"))
      (node (ref "USB2") (pin "3") (pinfunction "D+_3") (pintype "bidirectional"))
    )
    (net (code "65") (name "USB-") (class "Default")
      (node (ref "C24") (pin "2") (pinfunction "2_2") (pintype "passive"))
      (node (ref "R17") (pin "1") (pinfunction "1_1") (pintype "passive"))
      (node (ref "USB2") (pin "2") (pinfunction "D-_2") (pintype "bidirectional"))
    )
    (net (code "66") (name "VIN") (class "Default")
      (node (ref "C21") (pin "2") (pinfunction "2_2") (pintype "passive"))
      (node (ref "C5") (pin "2") (pinfunction "2_2") (pintype "passive"))
      (node (ref "CHRG2") (pin "4") (pinfunction "VIN_4") (pintype "power_in"))
      (node (ref "D4") (pin "-") (pinfunction "C_-") (pintype "passive"))
      (node (ref "D5") (pin "-") (pinfunction "C_-") (pintype "passive"))
      (node (ref "LDO2") (pin "1") (pinfunction "IN_1") (pintype "bidirectional"))
      (node (ref "LDO2") (pin "3") (pinfunction "EN_3") (pintype "bidirectional"))
      (node (ref "R12") (pin "2") (pinfunction "2_2") (pintype "passive"))
    )
    (net (code "67") (name "VLIPO") (class "Default")
      (node (ref "C20") (pin "1") (pinfunction "1_1") (pintype "passive"))
      (node (ref "CHRG2") (pin "3") (pinfunction "VBAT_3") (pintype "power_in"))
      (node (ref "D4") (pin "+") (pinfunction "A_+") (pintype "passive"))
      (node (ref "J2") (pin "2") (pinfunction "2_2") (pintype "passive"))
      (node (ref "R13") (pin "2") (pinfunction "2_2") (pintype "passive"))
    )
    (net (code "68") (name "VUSB") (class "Default")
      (node (ref "D5") (pin "+") (pinfunction "A_+") (pintype "passive"))
      (node (ref "U5") (pin "15") (pinfunction "VCC_15") (pintype "bidirectional"))
      (node (ref "USB2") (pin "1") (pinfunction "V+_1") (pintype "bidirectional"))
    )
    (net (code "69") (name "unconnected-(CORTEX1-NC{slash}TDI-Pad8)") (class "Default")
      (node (ref "CORTEX1") (pin "8") (pinfunction "NC/TDI_8") (pintype "bidirectional"))
    )
    (net (code "70") (name "unconnected-(SD2-DAT1-Pad8)") (class "Default")
      (node (ref "SD2") (pin "8") (pinfunction "DAT1_8") (pintype "bidirectional"))
    )
    (net (code "71") (name "unconnected-(SD2-DAT2-Pad1)") (class "Default")
      (node (ref "SD2") (pin "1") (pinfunction "DAT2_1") (pintype "bidirectional"))
    )
    (net (code "72") (name "unconnected-(SW1-2-PadA2)") (class "Default")
      (node (ref "SW1") (pin "A2") (pinfunction "2_A2") (pintype "passive"))
    )
    (net (code "73") (name "unconnected-(SW2-2-PadA2)") (class "Default")
      (node (ref "SW2") (pin "A2") (pinfunction "2_A2") (pintype "passive"))
    )
    (net (code "74") (name "unconnected-(U2-P0.02{slash}AIN0-Pad15)") (class "Default")
      (node (ref "U2") (pin "15") (pinfunction "P0.02/AIN0_15") (pintype "bidirectional"))
    )
    (net (code "75") (name "unconnected-(U2-P0.23-Pad41)") (class "Default")
      (node (ref "U2") (pin "41") (pinfunction "P0.23_41") (pintype "bidirectional"))
    )
    (net (code "76") (name "unconnected-(U2-P0.24-Pad40)") (class "Default")
      (node (ref "U2") (pin "40") (pinfunction "P0.24_40") (pintype "bidirectional"))
    )
    (net (code "77") (name "unconnected-(U3-D2{slash}I2C_SDA-Pad20)") (class "Default")
      (node (ref "U3") (pin "20") (pinfunction "D2/I2C_SDA_20") (pintype "bidirectional"))
    )
    (net (code "78") (name "unconnected-(U3-D3-Pad21)") (class "Default")
      (node (ref "U3") (pin "21") (pinfunction "D3_21") (pintype "bidirectional"))
    )
    (net (code "79") (name "unconnected-(U3-D4-Pad22)") (class "Default")
      (node (ref "U3") (pin "22") (pinfunction "D4_22") (pintype "bidirectional"))
    )
    (net (code "80") (name "unconnected-(U3-D5-Pad23)") (class "Default")
      (node (ref "U3") (pin "23") (pinfunction "D5_23") (pintype "bidirectional"))
    )
    (net (code "81") (name "unconnected-(U3-D6-Pad24)") (class "Default")
      (node (ref "U3") (pin "24") (pinfunction "D6_24") (pintype "bidirectional"))
    )
    (net (code "82") (name "unconnected-(U3-D7-Pad25)") (class "Default")
      (node (ref "U3") (pin "25") (pinfunction "D7_25") (pintype "bidirectional"))
    )
    (net (code "83") (name "unconnected-(U3-E{slash}RD-Pad17)") (class "Default")
      (node (ref "U3") (pin "17") (pinfunction "E/RD_17") (pintype "input"))
    )
    (net (code "84") (name "unconnected-(U3-NC-Pad7)") (class "Default")
      (node (ref "U3") (pin "7") (pinfunction "NC_7") (pintype "no_connect"))
    )
    (net (code "85") (name "unconnected-(U3-R{slash}W-Pad16)") (class "Default")
      (node (ref "U3") (pin "16") (pinfunction "R/W_16") (pintype "input"))
    )
    (net (code "86") (name "unconnected-(U4-INT{slash}CLKOUT-Pad7)") (class "Default")
      (node (ref "U4") (pin "7") (pinfunction "INT/CLKOUT_7") (pintype "bidirectional"))
    )
    (net (code "87") (name "unconnected-(U5-CBUS0-Pad18)") (class "Default")
      (node (ref "U5") (pin "18") (pinfunction "CBUS0_18") (pintype "bidirectional"))
    )
    (net (code "88") (name "unconnected-(U5-CBUS3-Pad19)") (class "Default")
      (node (ref "U5") (pin "19") (pinfunction "CBUS3_19") (pintype "bidirectional"))
    )
    (net (code "89") (name "unconnected-(U5-~{DCD}-Pad8)") (class "Default")
      (node (ref "U5") (pin "8") (pinfunction "~{DCD}_8") (pintype "bidirectional"))
    )
    (net (code "90") (name "unconnected-(U5-~{DSR}-Pad7)") (class "Default")
      (node (ref "U5") (pin "7") (pinfunction "~{DSR}_7") (pintype "bidirectional"))
    )
    (net (code "91") (name "unconnected-(U5-~{RI}-Pad5)") (class "Default")
      (node (ref "U5") (pin "5") (pinfunction "~{RI}_5") (pintype "bidirectional"))
    )
    (net (code "92") (name "unconnected-(U5-~{RTS}-Pad2)") (class "Default")
      (node (ref "U5") (pin "2") (pinfunction "~{RTS}_2") (pintype "bidirectional"))
    )
    (net (code "93") (name "unconnected-(USB2-ID-Pad4)") (class "Default")
      (node (ref "USB2") (pin "4") (pinfunction "ID_4") (pintype "bidirectional"))
    )
  )
)
